# BME280_Daughter_1_1.net
KiCad netlist of a schematic drawn in EAGLE
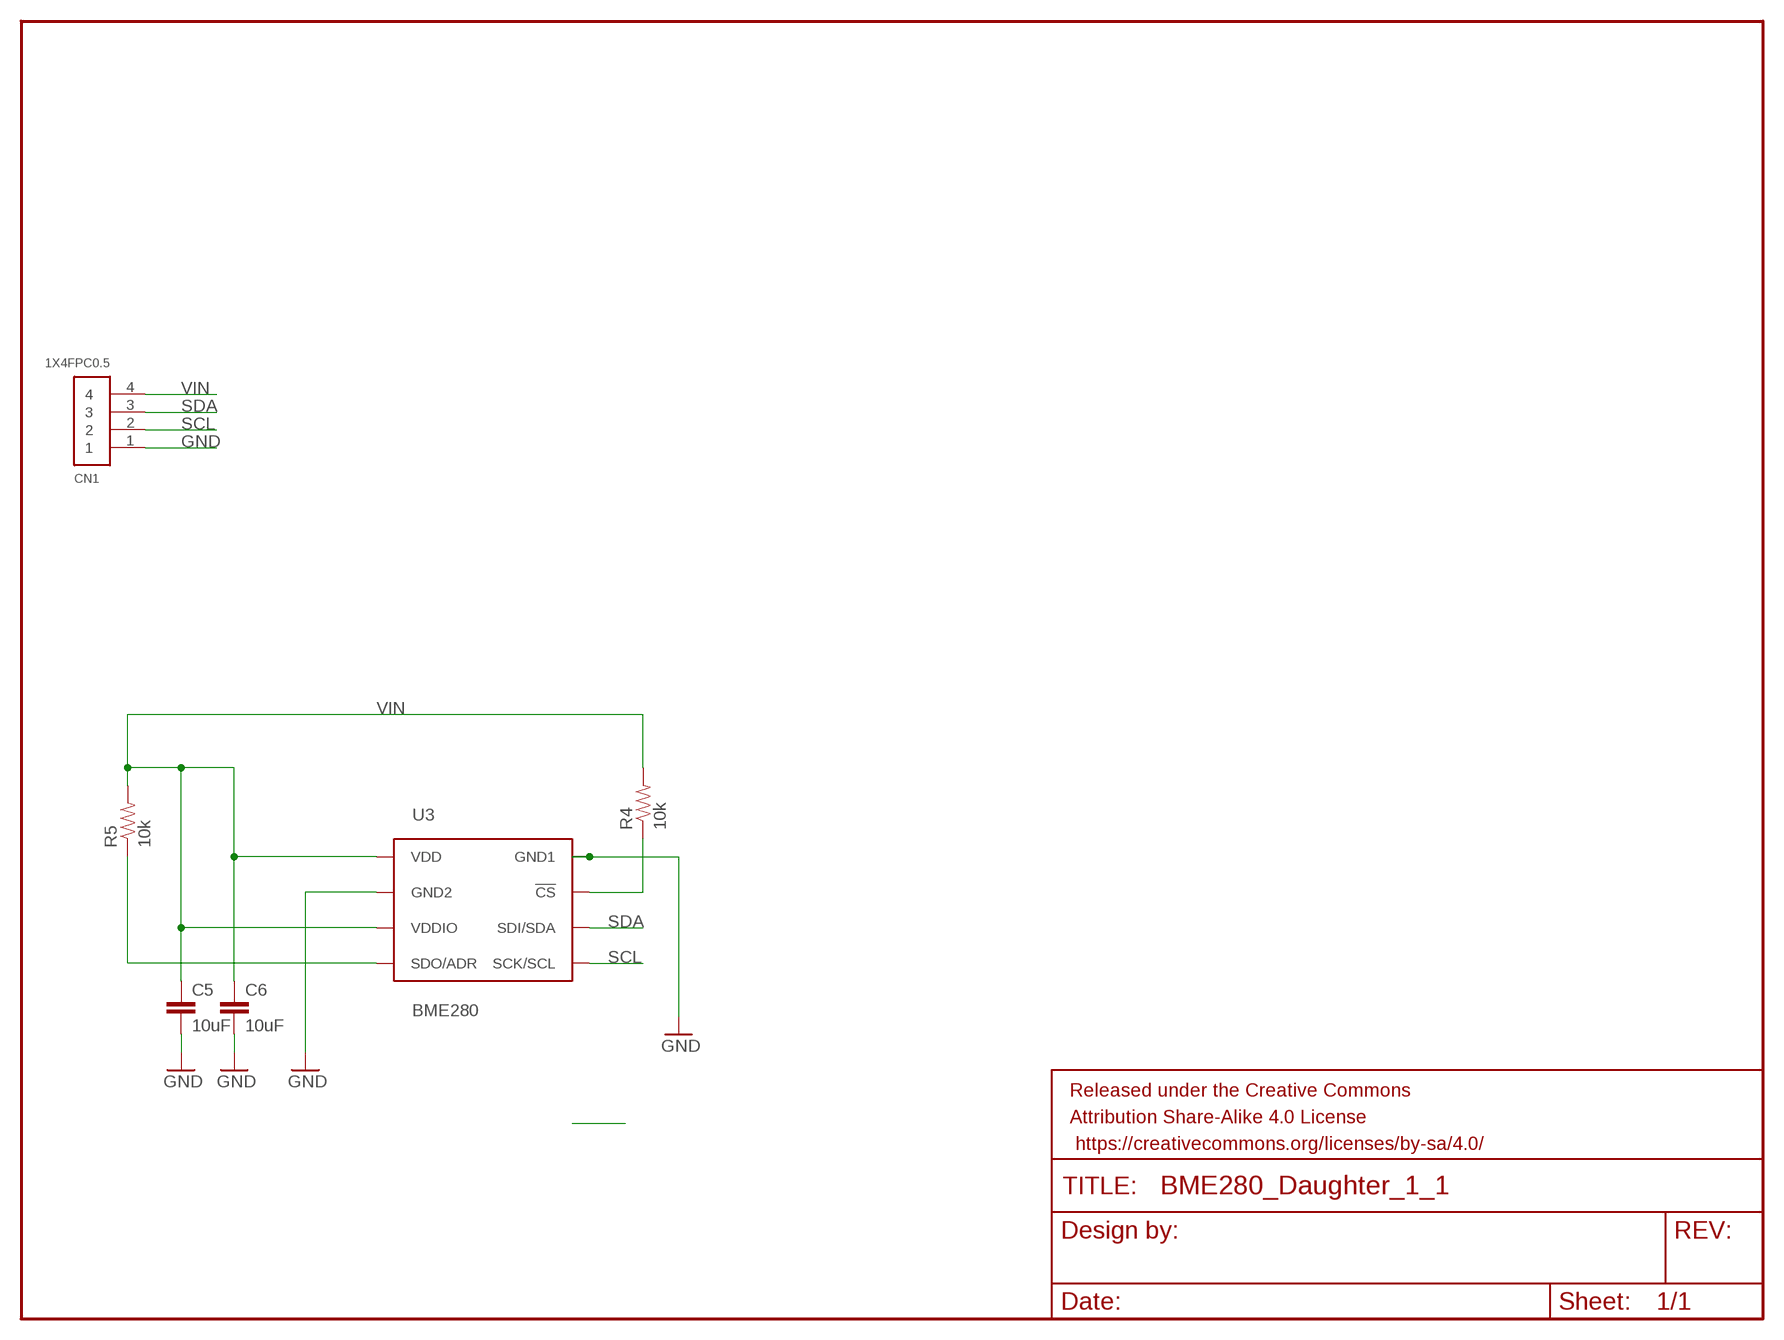
[diagram p0: schematic, sheet 1]

(export (version "E")
  (design (tool "Eeschema 10.0.6"))
  (components
    (comp (ref "C5")
      (value "10uF")
      (footprint "eagle-import:0805")
      (libsource (lib "eagle-import") (part "CAP0805"))
    )
    (comp (ref "C6")
      (value "10uF")
      (footprint "eagle-import:0805")
      (libsource (lib "eagle-import") (part "CAP0805"))
    )
    (comp (ref "CN1")
      (value "1X4FPC0.5")
      (footprint "eagle-import:FPC_0.5MM-4")
      (libsource (lib "eagle-import") (part "1X4FPC0.5"))
    )
    (comp (ref "FRAME1")
      (value "FRAME-LETTER")
      (footprint "eagle-import:CREATIVE_COMMONS")
      (libsource (lib "eagle-import") (part "FRAME-LETTER"))
    )
    (comp (ref "R4")
      (value "10k")
      (footprint "eagle-import:0805")
      (libsource (lib "eagle-import") (part "RESISTOR0805-RES"))
    )
    (comp (ref "R5")
      (value "10k")
      (footprint "eagle-import:0805")
      (libsource (lib "eagle-import") (part "RESISTOR0805-RES"))
    )
    (comp (ref "U3")
      (value "BME280")
      (footprint "eagle-import:BME280_LGA")
      (libsource (lib "eagle-import") (part "BME280"))
    )
  )
  (nets
    (net (code "1") (name "/SCL") (class "Default")
      (node (ref "CN1") (pin "2") (pinfunction "2_2") (pintype "bidirectional"))
      (node (ref "U3") (pin "P$4") (pinfunction "SCK/SCL_P$4") (pintype "bidirectional"))
    )
    (net (code "2") (name "/SDA") (class "Default")
      (node (ref "CN1") (pin "3") (pinfunction "3_3") (pintype "bidirectional"))
      (node (ref "U3") (pin "P$3") (pinfunction "SDI/SDA_P$3") (pintype "bidirectional"))
    )
    (net (code "3") (name "/VIN") (class "Default")
      (node (ref "C5") (pin "1") (pinfunction "1_1") (pintype "passive"))
      (node (ref "C6") (pin "1") (pinfunction "1_1") (pintype "passive"))
      (node (ref "CN1") (pin "4") (pinfunction "4_4") (pintype "bidirectional"))
      (node (ref "R4") (pin "2") (pinfunction "2_2") (pintype "passive"))
      (node (ref "R5") (pin "2") (pinfunction "2_2") (pintype "passive"))
      (node (ref "U3") (pin "P$6") (pinfunction "VDDIO_P$6") (pintype "bidirectional"))
      (node (ref "U3") (pin "P$8") (pinfunction "VDD_P$8") (pintype "bidirectional"))
    )
    (net (code "4") (name "GND") (class "Default")
      (node (ref "C5") (pin "2") (pinfunction "2_2") (pintype "passive"))
      (node (ref "C6") (pin "2") (pinfunction "2_2") (pintype "passive"))
      (node (ref "CN1") (pin "1") (pinfunction "1_1") (pintype "bidirectional"))
      (node (ref "U3") (pin "P$1") (pinfunction "GND1_P$1") (pintype "bidirectional"))
      (node (ref "U3") (pin "P$7") (pinfunction "GND2_P$7") (pintype "bidirectional"))
    )
    (net (code "5") (name "Net-(U3-SDO{slash}ADR)") (class "Default")
      (node (ref "R5") (pin "1") (pinfunction "1_1") (pintype "passive"))
      (node (ref "U3") (pin "P$5") (pinfunction "SDO/ADR_P$5") (pintype "bidirectional"))
    )
    (net (code "6") (name "Net-(U3-~{CS})") (class "Default")
      (node (ref "R4") (pin "1") (pinfunction "1_1") (pintype "passive"))
      (node (ref "U3") (pin "P$2") (pinfunction "~{CS}_P$2") (pintype "bidirectional"))
    )
  )
)
